# K210_V1.net
KiCad netlist of a schematic drawn in Altium Designer
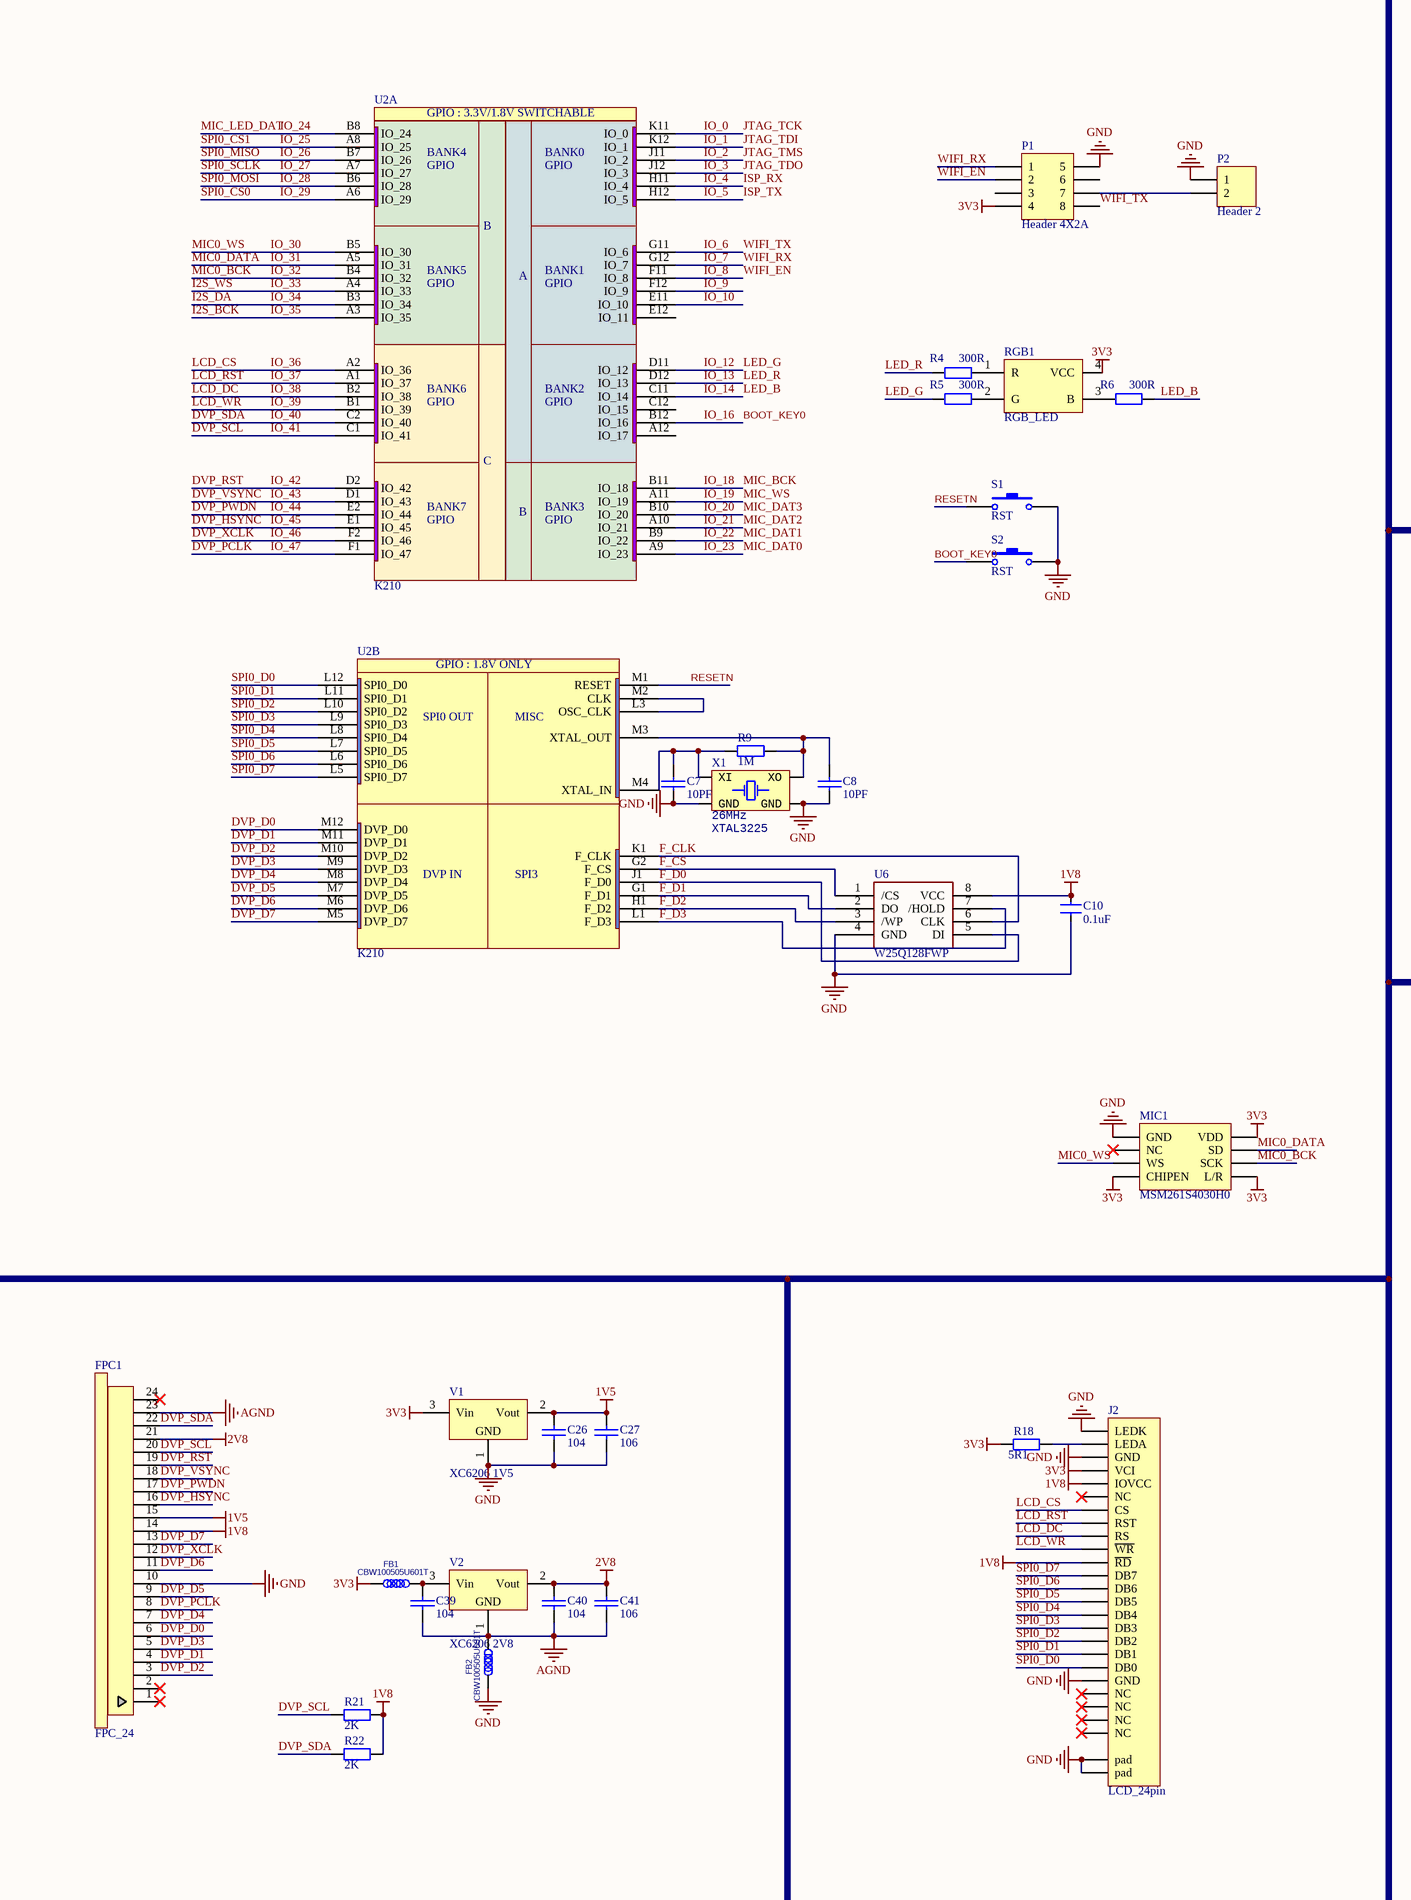
[diagram p0: K210_V1.SchDoc, left]
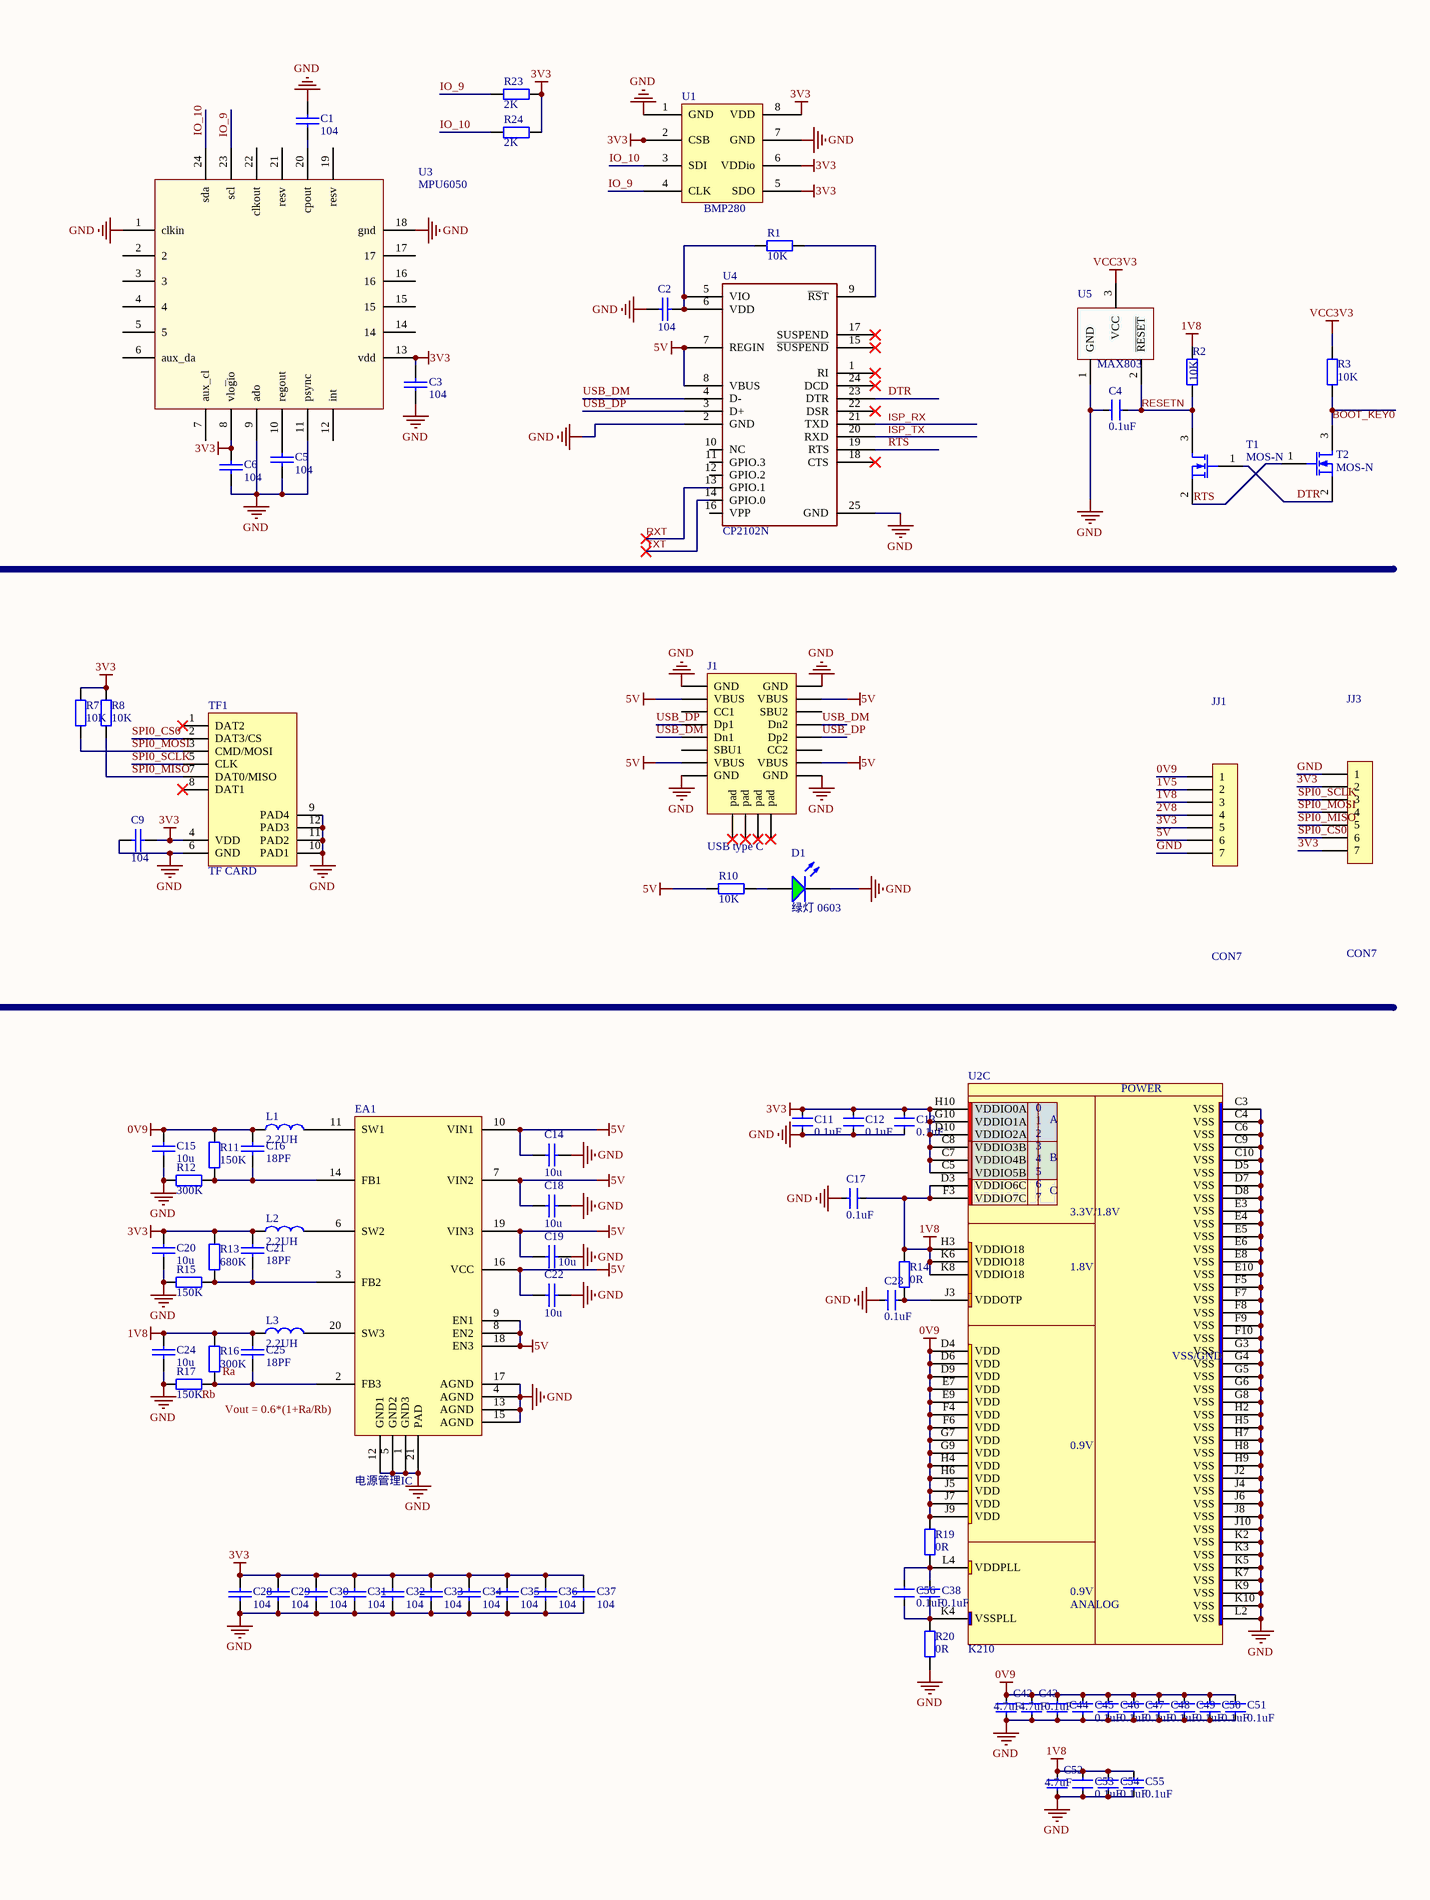
[diagram p1: K210_V1.SchDoc, right]

(export (version "E")
  (design (tool "Eeschema 10.0.6"))
  (components
    (comp (ref "C1") (value "104") (footprint "0603_C") (libsource (lib "XKZ") (part "CAP")))
    (comp (ref "C2") (value "104") (footprint "0603_C") (libsource (lib "XKZ") (part "CAP")))
    (comp (ref "C3") (value "104") (footprint "0603_C") (libsource (lib "XKZ") (part "CAP")))
    (comp (ref "C4")
      (value "0.1uF")
      (footprint "0603_C")
      (description "普通小电容")
      (libsource (lib "LIB_MANGO") (part "CAP"))
    )
    (comp (ref "C5") (value "104") (footprint "0603_C") (libsource (lib "XKZ") (part "CAP")))
    (comp (ref "C6") (value "104") (footprint "0603_C") (libsource (lib "XKZ") (part "CAP")))
    (comp (ref "C7") (value "10PF") (footprint "0603_C") (libsource (lib "XKZ") (part "CAP")))
    (comp (ref "C8") (value "10PF") (footprint "0603_C") (libsource (lib "XKZ") (part "CAP")))
    (comp (ref "C9") (value "104") (footprint "0603_C") (libsource (lib "XKZ") (part "CAP")))
    (comp (ref "C10")
      (value "0.1uF")
      (footprint "0603_C")
      (description "普通小电容")
      (libsource (lib "LIB_MANGO") (part "CAP"))
    )
    (comp (ref "C11")
      (value "0.1uF")
      (footprint "0603_C")
      (description "普通小电容")
      (libsource (lib "LIB_MANGO") (part "CAP"))
    )
    (comp (ref "C12")
      (value "0.1uF")
      (footprint "0603_C")
      (description "普通小电容")
      (libsource (lib "LIB_MANGO") (part "CAP"))
    )
    (comp (ref "C13")
      (value "0.1uF")
      (footprint "0603_C")
      (description "普通小电容")
      (libsource (lib "LIB_MANGO") (part "CAP"))
    )
    (comp (ref "C14") (value "10u") (footprint "0603_C") (libsource (lib "XKZ") (part "CAP")))
    (comp (ref "C15") (value "10u") (footprint "0603_C") (libsource (lib "XKZ") (part "CAP")))
    (comp (ref "C16") (value "18PF") (footprint "0603_C") (libsource (lib "XKZ") (part "CAP")))
    (comp (ref "C17")
      (value "0.1uF")
      (footprint "0603_C")
      (description "普通小电容")
      (libsource (lib "LIB_MANGO") (part "CAP"))
    )
    (comp (ref "C18") (value "10u") (footprint "0603_C") (libsource (lib "XKZ") (part "CAP")))
    (comp (ref "C19") (value "10u") (footprint "0603_C") (libsource (lib "XKZ") (part "CAP")))
    (comp (ref "C20") (value "10u") (footprint "0603_C") (libsource (lib "XKZ") (part "CAP")))
    (comp (ref "C21") (value "18PF") (footprint "0603_C") (libsource (lib "XKZ") (part "CAP")))
    (comp (ref "C22") (value "10u") (footprint "0603_C") (libsource (lib "XKZ") (part "CAP")))
    (comp (ref "C23")
      (value "0.1uF")
      (footprint "0603_C")
      (description "普通小电容")
      (libsource (lib "LIB_MANGO") (part "CAP"))
    )
    (comp (ref "C24") (value "10u") (footprint "0603_C") (libsource (lib "XKZ") (part "CAP")))
    (comp (ref "C25") (value "18PF") (footprint "0603_C") (libsource (lib "XKZ") (part "CAP")))
    (comp (ref "C26") (value "104") (footprint "0603_C") (libsource (lib "XKZ") (part "CAP")))
    (comp (ref "C27") (value "106") (footprint "0603_C") (libsource (lib "XKZ") (part "CAP")))
    (comp (ref "C28") (value "104") (footprint "0603_C") (libsource (lib "XKZ") (part "CAP")))
    (comp (ref "C29") (value "104") (footprint "0603_C") (libsource (lib "XKZ") (part "CAP")))
    (comp (ref "C30") (value "104") (footprint "0603_C") (libsource (lib "XKZ") (part "CAP")))
    (comp (ref "C31") (value "104") (footprint "0603_C") (libsource (lib "XKZ") (part "CAP")))
    (comp (ref "C32") (value "104") (footprint "0603_C") (libsource (lib "XKZ") (part "CAP")))
    (comp (ref "C33") (value "104") (footprint "0603_C") (libsource (lib "XKZ") (part "CAP")))
    (comp (ref "C34") (value "104") (footprint "0603_C") (libsource (lib "XKZ") (part "CAP")))
    (comp (ref "C35") (value "104") (footprint "0603_C") (libsource (lib "XKZ") (part "CAP")))
    (comp (ref "C36") (value "104") (footprint "0603_C") (libsource (lib "XKZ") (part "CAP")))
    (comp (ref "C37") (value "104") (footprint "0603_C") (libsource (lib "XKZ") (part "CAP")))
    (comp (ref "C38")
      (value "0.1uF")
      (footprint "0603_C")
      (description "普通小电容")
      (libsource (lib "LIB_MANGO") (part "CAP"))
    )
    (comp (ref "C39") (value "104") (footprint "0603_C") (libsource (lib "XKZ") (part "CAP")))
    (comp (ref "C40") (value "104") (footprint "0603_C") (libsource (lib "XKZ") (part "CAP")))
    (comp (ref "C41") (value "106") (footprint "0603_C") (libsource (lib "XKZ") (part "CAP")))
    (comp (ref "C42")
      (value "4.7uF")
      (footprint "0603_C")
      (description "普通小电容")
      (libsource (lib "LIB_MANGO") (part "CAP"))
    )
    (comp (ref "C43")
      (value "4.7uF")
      (footprint "0603_C")
      (description "普通小电容")
      (libsource (lib "LIB_MANGO") (part "CAP"))
    )
    (comp (ref "C44")
      (value "0.1uF")
      (footprint "0603_C")
      (description "普通小电容")
      (libsource (lib "LIB_MANGO") (part "CAP"))
    )
    (comp (ref "C45")
      (value "0.1uF")
      (footprint "0603_C")
      (description "普通小电容")
      (libsource (lib "LIB_MANGO") (part "CAP"))
    )
    (comp (ref "C46")
      (value "0.1uF")
      (footprint "0603_C")
      (description "普通小电容")
      (libsource (lib "LIB_MANGO") (part "CAP"))
    )
    (comp (ref "C47")
      (value "0.1uF")
      (footprint "0603_C")
      (description "普通小电容")
      (libsource (lib "LIB_MANGO") (part "CAP"))
    )
    (comp (ref "C48")
      (value "0.1uF")
      (footprint "0603_C")
      (description "普通小电容")
      (libsource (lib "LIB_MANGO") (part "CAP"))
    )
    (comp (ref "C49")
      (value "0.1uF")
      (footprint "0603_C")
      (description "普通小电容")
      (libsource (lib "LIB_MANGO") (part "CAP"))
    )
    (comp (ref "C50")
      (value "0.1uF")
      (footprint "0603_C")
      (description "普通小电容")
      (libsource (lib "LIB_MANGO") (part "CAP"))
    )
    (comp (ref "C51")
      (value "0.1uF")
      (footprint "0603_C")
      (description "普通小电容")
      (libsource (lib "LIB_MANGO") (part "CAP"))
    )
    (comp (ref "C52")
      (value "4.7uF")
      (footprint "0603_C")
      (description "普通小电容")
      (libsource (lib "LIB_MANGO") (part "CAP"))
    )
    (comp (ref "C53")
      (value "0.1uF")
      (footprint "0603_C")
      (description "普通小电容")
      (libsource (lib "LIB_MANGO") (part "CAP"))
    )
    (comp (ref "C54")
      (value "0.1uF")
      (footprint "0603_C")
      (description "普通小电容")
      (libsource (lib "LIB_MANGO") (part "CAP"))
    )
    (comp (ref "C55")
      (value "0.1uF")
      (footprint "0603_C")
      (description "普通小电容")
      (libsource (lib "LIB_MANGO") (part "CAP"))
    )
    (comp (ref "C56")
      (value "0.1uF")
      (footprint "0603_C")
      (description "普通小电容")
      (libsource (lib "LIB_MANGO") (part "CAP"))
    )
    (comp (ref "D1")
      (value "绿灯 0603")
      (footprint "0603_LED")
      (description "发光二极管")
      (libsource (lib "Miscellaneous Devices LC") (part "0603 绿灯"))
    )
    (comp (ref "EA1") (value "电源管理IC") (footprint "QFN20 3x3_M") (libsource (lib "XKZ") (part "EA3036")))
    (comp (ref "FB1") (value "CBW100505U601T") (footprint "0603_R") (libsource (lib "XKZ") (part "FB")))
    (comp (ref "FB2") (value "CBW100505U601T") (footprint "0603_R") (libsource (lib "XKZ") (part "FB")))
    (comp (ref "FPC1") (value "FPC_24") (footprint "FPC_24") (libsource (lib "XKZ") (part "FPC_24")))
    (comp (ref "J1")
      (value "USB type C")
      (footprint "USB Type-C-16Pin_A")
      (libsource (lib "XKZ") (part "USB_C"))
    )
    (comp (ref "J2") (value "LCD_24pin") (footprint "OV7740") (libsource (lib "XKZ") (part "LCD_24pin")))
    (comp (ref "JJ1") (value "CON7") (footprint "HDR2.54-LI-7P") (libsource (lib "XKZ") (part "CON7")))
    (comp (ref "JJ3") (value "CON7") (footprint "HDR2.54-LI-7P") (libsource (lib "XKZ") (part "CON7")))
    (comp (ref "L1")
      (value "2.2UH")
      (footprint "NR3015")
      (description "电感")
      (libsource (lib "XKZ") (part "L1"))
    )
    (comp (ref "L2")
      (value "2.2UH")
      (footprint "NR3015")
      (description "电感")
      (libsource (lib "XKZ") (part "L1"))
    )
    (comp (ref "L3")
      (value "2.2UH")
      (footprint "NR3015")
      (description "电感")
      (libsource (lib "XKZ") (part "L1"))
    )
    (comp (ref "MIC1")
      (value "MSM261S4030H0")
      (footprint "MSM261S4030H0")
      (libsource (lib "XKZ") (part "MSM261S4030H0"))
    )
    (comp (ref "P1")
      (value "Header 4X2A")
      (footprint "HDR2X4_CEN")
      (description "Header, 4-Pin, Dual row")
      (fields (field (name "PUBLISHER") "Altium Limited"))
      (libsource (lib "Miscellaneous Connectors") (part "Header 4X2A"))
    )
    (comp (ref "P2")
      (value "Header 2")
      (footprint "HDR1X2")
      (description "Header, 2-Pin")
      (fields (field (name "PUBLISHER") "Altium Limited"))
      (libsource (lib "Miscellaneous Connectors") (part "Header 2"))
    )
    (comp (ref "R1")
      (value "10K")
      (footprint "0603_R")
      (description "普通电阻")
      (libsource (lib "") (part "RES_2"))
    )
    (comp (ref "R2")
      (value "10K")
      (footprint "0603_R")
      (description "普通电阻")
      (libsource (lib "LIB_MANGO") (part "RES"))
    )
    (comp (ref "R3")
      (value "10K")
      (footprint "0603_R")
      (description "普通电阻")
      (libsource (lib "") (part "RES_1"))
    )
    (comp (ref "R4")
      (value "300R")
      (footprint "0603_R")
      (description "Resistor")
      (fields (field (name "Comment") "1K") (field (name "PUBLISHER") "Altium Limited"))
      (libsource (lib "Miscellaneous Devices") (part "Res2"))
    )
    (comp (ref "R5")
      (value "300R")
      (footprint "0603_R")
      (description "Resistor")
      (fields (field (name "Comment") "1K") (field (name "PUBLISHER") "Altium Limited"))
      (libsource (lib "Miscellaneous Devices") (part "Res2"))
    )
    (comp (ref "R6")
      (value "300R")
      (footprint "0603_R")
      (description "Resistor")
      (fields (field (name "Comment") "1K") (field (name "PUBLISHER") "Altium Limited"))
      (libsource (lib "Miscellaneous Devices") (part "Res2"))
    )
    (comp (ref "R7")
      (value "10K")
      (footprint "0603_R")
      (description "Resistor")
      (fields (field (name "Comment") "Res2") (field (name "PUBLISHER") "Altium Limited"))
      (libsource (lib "XKZ") (part "Res2"))
    )
    (comp (ref "R8")
      (value "10K")
      (footprint "0603_R")
      (description "Resistor")
      (fields (field (name "Comment") "Res2") (field (name "PUBLISHER") "Altium Limited"))
      (libsource (lib "XKZ") (part "Res2"))
    )
    (comp (ref "R9")
      (value "1M")
      (footprint "0603_R")
      (description "Resistor")
      (fields (field (name "Comment") "Res2") (field (name "PUBLISHER") "Altium Limited"))
      (libsource (lib "") (part "Res2_2"))
    )
    (comp (ref "R10")
      (value "10K")
      (footprint "0603_R")
      (description "Resistor")
      (fields (field (name "Comment") "Res2") (field (name "PUBLISHER") "Altium Limited"))
      (libsource (lib "") (part "Res2_1"))
    )
    (comp (ref "R11")
      (value "150K")
      (footprint "0603_R")
      (description "Resistor")
      (fields (field (name "Comment") "Res2") (field (name "PUBLISHER") "Altium Limited"))
      (libsource (lib "") (part "Res2_3"))
    )
    (comp (ref "R12")
      (value "300K")
      (footprint "0603_R")
      (description "Resistor")
      (fields (field (name "Comment") "Res2") (field (name "PUBLISHER") "Altium Limited"))
      (libsource (lib "") (part "Res2_1"))
    )
    (comp (ref "R13")
      (value "680K")
      (footprint "0603_R")
      (description "Resistor")
      (fields (field (name "Comment") "Res2") (field (name "PUBLISHER") "Altium Limited"))
      (libsource (lib "") (part "Res2_3"))
    )
    (comp (ref "R14")
      (value "0R")
      (footprint "0603_R")
      (description "普通电阻")
      (libsource (lib "") (part "RES_1"))
    )
    (comp (ref "R15")
      (value "150K")
      (footprint "0603_R")
      (description "Resistor")
      (fields (field (name "Comment") "Res2") (field (name "PUBLISHER") "Altium Limited"))
      (libsource (lib "") (part "Res2_1"))
    )
    (comp (ref "R16")
      (value "300K")
      (footprint "0603_R")
      (description "Resistor")
      (fields (field (name "Comment") "Res2") (field (name "PUBLISHER") "Altium Limited"))
      (libsource (lib "") (part "Res2_3"))
    )
    (comp (ref "R17")
      (value "150K")
      (footprint "0603_R")
      (description "Resistor")
      (fields (field (name "Comment") "Res2") (field (name "PUBLISHER") "Altium Limited"))
      (libsource (lib "") (part "Res2_1"))
    )
    (comp (ref "R18")
      (value "5R1")
      (footprint "0603_R")
      (description "Resistor")
      (fields (field (name "Comment") "Res2") (field (name "PUBLISHER") "Altium Limited"))
      (libsource (lib "") (part "Res2_2"))
    )
    (comp (ref "R19")
      (value "0R")
      (footprint "0603_R")
      (description "普通电阻")
      (libsource (lib "LIB_MANGO") (part "RES"))
    )
    (comp (ref "R20")
      (value "0R")
      (footprint "0603_R")
      (description "普通电阻")
      (libsource (lib "LIB_MANGO") (part "RES"))
    )
    (comp (ref "R21")
      (value "2K")
      (footprint "0603_R")
      (description "Resistor")
      (fields (field (name "Comment") "Res2") (field (name "PUBLISHER") "Altium Limited"))
      (libsource (lib "") (part "Res2_2"))
    )
    (comp (ref "R22")
      (value "2K")
      (footprint "0603_R")
      (description "Resistor")
      (fields (field (name "Comment") "Res2") (field (name "PUBLISHER") "Altium Limited"))
      (libsource (lib "") (part "Res2_2"))
    )
    (comp (ref "R23")
      (value "2K")
      (footprint "0603_R")
      (description "Resistor")
      (fields (field (name "Comment") "Res2") (field (name "PUBLISHER") "Altium Limited"))
      (libsource (lib "") (part "Res2_2"))
    )
    (comp (ref "R24")
      (value "2K")
      (footprint "0603_R")
      (description "Resistor")
      (fields (field (name "Comment") "Res2") (field (name "PUBLISHER") "Altium Limited"))
      (libsource (lib "") (part "Res2_2"))
    )
    (comp (ref "RGB1")
      (value "RGB_LED")
      (footprint "LED_3528_RGB")
      (description "三色高亮LED")
      (libsource (lib "NT-SchLibrary") (part "RGB_LED"))
    )
    (comp (ref "S1")
      (value "RST")
      (footprint "KEY_1")
      (description "Switch")
      (fields (field (name "PUBLISHER") "Altium Limited"))
      (libsource (lib "自创 (1)") (part "SW-PB"))
    )
    (comp (ref "S2")
      (value "RST")
      (footprint "KEY_1")
      (description "Switch")
      (fields (field (name "PUBLISHER") "Altium Limited"))
      (libsource (lib "自创 (1)") (part "SW-PB"))
    )
    (comp (ref "T1") (value "MOS-N") (footprint "SOT23-3N") (libsource (lib "LIB_MANGO") (part "MOS-N")))
    (comp (ref "T2") (value "MOS-N") (footprint "SOT23-3N") (libsource (lib "LIB_MANGO") (part "MOS-N")))
    (comp (ref "TF1") (value "TF CARD") (footprint "TF卡座") (libsource (lib "XKZ") (part "SD_Card_flip")))
    (comp (ref "U1") (value "BMP280") (footprint "BMP280") (libsource (lib "NT-SchLibrary") (part "BMP280")))
    (comp (ref "U2")
      (value "K210")
      (footprint "BGA144C65P12X12_800X800X95")
      (description "Canaan Kendryte K210 AI SoC")
      (libsource (lib "Vowstar_MCU") (part "K210"))
    )
    (comp (ref "U3")
      (value "MPU6050")
      (footprint "QFN24 4x4_M")
      (libsource (lib "NT-SchLibrary") (part "MPU6050"))
    )
    (comp (ref "U4")
      (value "CP2102N")
      (footprint "QFN24 4x4_N")
      (libsource (lib "LIB_MANGO") (part "CP2104"))
    )
    (comp (ref "U5") (value "MAX803") (footprint "SOT23-3N") (libsource (lib "LIB_MANGO") (part "MAX809")))
    (comp (ref "U6")
      (value "W25Q128FWP")
      (footprint "WSON8")
      (libsource (lib "LIB_MANGO") (part "SPIFLASH_SOP8W"))
    )
    (comp (ref "V1")
      (value "XC6206 1V5")
      (footprint "SOT23-3N")
      (description "低压差线性稳压芯片")
      (fields (field (name "版权归属") "源创客"))
      (libsource (lib "XKZ") (part "XC6206P332MR"))
    )
    (comp (ref "V2")
      (value "XC6206 2V8")
      (footprint "SOT23-3N")
      (description "低压差线性稳压芯片")
      (fields (field (name "版权归属") "源创客"))
      (libsource (lib "XKZ") (part "XC6206P332MR"))
    )
    (comp (ref "X1")
      (value "26MHz")
      (footprint "XT_3225_4")
      (description "Crystal Oscillator")
      (fields (field (name "TYPE") "XTAL3225"))
      (libsource (lib "XKZ") (part "XTAL_3225_4P"))
    )
  )
  (nets
    (net (code "1") (name "/BOOT_KEY0") (class "Default")
      (node (ref "R3") (pin "2") (pinfunction "2_2") (pintype "passive"))
      (node (ref "S2") (pin "1") (pinfunction "1_1") (pintype "passive"))
      (node (ref "T2") (pin "3") (pinfunction "3_3") (pintype "passive"))
      (node (ref "U2") (pin "B12") (pinfunction "IO_16_B12") (pintype "passive"))
    )
    (net (code "2") (name "/DTR") (class "Default")
      (node (ref "T1") (pin "1") (pinfunction "1_1") (pintype "passive"))
      (node (ref "T2") (pin "2") (pinfunction "2_2") (pintype "passive"))
      (node (ref "U4") (pin "23") (pinfunction "DTR_23") (pintype "passive"))
    )
    (net (code "3") (name "/DVP_D0") (class "Default")
      (node (ref "FPC1") (pin "6") (pinfunction "6_6") (pintype "passive"))
      (node (ref "U2") (pin "M12") (pinfunction "DVP_D0_M12") (pintype "passive"))
    )
    (net (code "4") (name "/DVP_D1") (class "Default")
      (node (ref "FPC1") (pin "4") (pinfunction "4_4") (pintype "passive"))
      (node (ref "U2") (pin "M11") (pinfunction "DVP_D1_M11") (pintype "passive"))
    )
    (net (code "5") (name "/DVP_D2") (class "Default")
      (node (ref "FPC1") (pin "3") (pinfunction "3_3") (pintype "passive"))
      (node (ref "U2") (pin "M10") (pinfunction "DVP_D2_M10") (pintype "passive"))
    )
    (net (code "6") (name "/DVP_D3") (class "Default")
      (node (ref "FPC1") (pin "5") (pinfunction "5_5") (pintype "passive"))
      (node (ref "U2") (pin "M9") (pinfunction "DVP_D3_M9") (pintype "passive"))
    )
    (net (code "7") (name "/DVP_D4") (class "Default")
      (node (ref "FPC1") (pin "7") (pinfunction "7_7") (pintype "passive"))
      (node (ref "U2") (pin "M8") (pinfunction "DVP_D4_M8") (pintype "passive"))
    )
    (net (code "8") (name "/DVP_D5") (class "Default")
      (node (ref "FPC1") (pin "9") (pinfunction "9_9") (pintype "passive"))
      (node (ref "U2") (pin "M7") (pinfunction "DVP_D5_M7") (pintype "passive"))
    )
    (net (code "9") (name "/DVP_D6") (class "Default")
      (node (ref "FPC1") (pin "11") (pinfunction "11_11") (pintype "passive"))
      (node (ref "U2") (pin "M6") (pinfunction "DVP_D6_M6") (pintype "passive"))
    )
    (net (code "10") (name "/DVP_D7") (class "Default")
      (node (ref "FPC1") (pin "13") (pinfunction "13_13") (pintype "passive"))
      (node (ref "U2") (pin "M5") (pinfunction "DVP_D7_M5") (pintype "passive"))
    )
    (net (code "11") (name "/DVP_HSYNC") (class "Default")
      (node (ref "FPC1") (pin "16") (pinfunction "16_16") (pintype "passive"))
      (node (ref "U2") (pin "E1") (pinfunction "IO_45_E1") (pintype "passive"))
    )
    (net (code "12") (name "/DVP_PCLK") (class "Default")
      (node (ref "FPC1") (pin "8") (pinfunction "8_8") (pintype "passive"))
      (node (ref "U2") (pin "F1") (pinfunction "IO_47_F1") (pintype "passive"))
    )
    (net (code "13") (name "/DVP_PWDN") (class "Default")
      (node (ref "FPC1") (pin "17") (pinfunction "17_17") (pintype "passive"))
      (node (ref "U2") (pin "E2") (pinfunction "IO_44_E2") (pintype "passive"))
    )
    (net (code "14") (name "/DVP_RST") (class "Default")
      (node (ref "FPC1") (pin "19") (pinfunction "19_19") (pintype "passive"))
      (node (ref "U2") (pin "D2") (pinfunction "IO_42_D2") (pintype "passive"))
    )
    (net (code "15") (name "/DVP_SCL") (class "Default")
      (node (ref "FPC1") (pin "20") (pinfunction "20_20") (pintype "passive"))
      (node (ref "R21") (pin "2") (pinfunction "2_2") (pintype "passive"))
      (node (ref "U2") (pin "C1") (pinfunction "IO_41_C1") (pintype "passive"))
    )
    (net (code "16") (name "/DVP_SDA") (class "Default")
      (node (ref "FPC1") (pin "22") (pinfunction "22_22") (pintype "passive"))
      (node (ref "R22") (pin "2") (pinfunction "2_2") (pintype "passive"))
      (node (ref "U2") (pin "C2") (pinfunction "IO_40_C2") (pintype "passive"))
    )
    (net (code "17") (name "/DVP_VSYNC") (class "Default")
      (node (ref "FPC1") (pin "18") (pinfunction "18_18") (pintype "passive"))
      (node (ref "U2") (pin "D1") (pinfunction "IO_43_D1") (pintype "passive"))
    )
    (net (code "18") (name "/DVP_XCLK") (class "Default")
      (node (ref "FPC1") (pin "12") (pinfunction "12_12") (pintype "passive"))
      (node (ref "U2") (pin "F2") (pinfunction "IO_46_F2") (pintype "passive"))
    )
    (net (code "19") (name "/F_CLK") (class "Default")
      (node (ref "U2") (pin "K1") (pinfunction "F_CLK_K1") (pintype "passive"))
      (node (ref "U6") (pin "6") (pinfunction "CLK_6") (pintype "passive"))
    )
    (net (code "20") (name "/F_CS") (class "Default")
      (node (ref "U2") (pin "G2") (pinfunction "F_CS_G2") (pintype "passive"))
      (node (ref "U6") (pin "1") (pinfunction "/CS_1") (pintype "passive"))
    )
    (net (code "21") (name "/F_D0") (class "Default")
      (node (ref "U2") (pin "J1") (pinfunction "F_D0_J1") (pintype "passive"))
      (node (ref "U6") (pin "5") (pinfunction "DI_5") (pintype "passive"))
    )
    (net (code "22") (name "/F_D1") (class "Default")
      (node (ref "U2") (pin "G1") (pinfunction "F_D1_G1") (pintype "passive"))
      (node (ref "U6") (pin "2") (pinfunction "DO_2") (pintype "passive"))
    )
    (net (code "23") (name "/F_D2") (class "Default")
      (node (ref "U2") (pin "H1") (pinfunction "F_D2_H1") (pintype "passive"))
      (node (ref "U6") (pin "3") (pinfunction "/WP_3") (pintype "passive"))
    )
    (net (code "24") (name "/F_D3") (class "Default")
      (node (ref "U2") (pin "L1") (pinfunction "F_D3_L1") (pintype "passive"))
      (node (ref "U6") (pin "7") (pinfunction "/HOLD_7") (pintype "passive"))
    )
    (net (code "25") (name "/I2S_BCK") (class "Default")
      (node (ref "U2") (pin "A3") (pinfunction "IO_35_A3") (pintype "passive"))
    )
    (net (code "26") (name "/I2S_DA") (class "Default")
      (node (ref "U2") (pin "B3") (pinfunction "IO_34_B3") (pintype "passive"))
    )
    (net (code "27") (name "/I2S_WS") (class "Default")
      (node (ref "U2") (pin "A4") (pinfunction "IO_33_A4") (pintype "passive"))
    )
    (net (code "28") (name "/IO_0") (class "Default")
      (node (ref "U2") (pin "K11") (pinfunction "IO_0_K11") (pintype "passive"))
    )
    (net (code "29") (name "/IO_1") (class "Default")
      (node (ref "U2") (pin "K12") (pinfunction "IO_1_K12") (pintype "passive"))
    )
    (net (code "30") (name "/IO_2") (class "Default")
      (node (ref "U2") (pin "J11") (pinfunction "IO_2_J11") (pintype "passive"))
    )
    (net (code "31") (name "/IO_3") (class "Default")
      (node (ref "U2") (pin "J12") (pinfunction "IO_3_J12") (pintype "passive"))
    )
    (net (code "32") (name "/IO_4") (class "Default")
      (node (ref "U2") (pin "H11") (pinfunction "IO_4_H11") (pintype "passive"))
      (node (ref "U4") (pin "21") (pinfunction "TXD_21") (pintype "passive"))
    )
    (net (code "33") (name "/IO_5") (class "Default")
      (node (ref "U2") (pin "H12") (pinfunction "IO_5_H12") (pintype "passive"))
      (node (ref "U4") (pin "20") (pinfunction "RXD_20") (pintype "passive"))
    )
    (net (code "34") (name "/IO_6") (class "Default")
      (node (ref "P1") (pin "8") (pinfunction "8_8") (pintype "passive"))
      (node (ref "U2") (pin "G11") (pinfunction "IO_6_G11") (pintype "passive"))
    )
    (net (code "35") (name "/IO_7") (class "Default")
      (node (ref "P1") (pin "1") (pinfunction "1_1") (pintype "passive"))
      (node (ref "U2") (pin "G12") (pinfunction "IO_7_G12") (pintype "passive"))
    )
    (net (code "36") (name "/IO_8") (class "Default")
      (node (ref "P1") (pin "2") (pinfunction "2_2") (pintype "passive"))
      (node (ref "U2") (pin "F11") (pinfunction "IO_8_F11") (pintype "passive"))
    )
    (net (code "37") (name "/IO_9") (class "Default")
      (node (ref "R23") (pin "2") (pinfunction "2_2") (pintype "passive"))
      (node (ref "U1") (pin "4") (pinfunction "CLK_4") (pintype "power_in"))
      (node (ref "U2") (pin "F12") (pinfunction "IO_9_F12") (pintype "passive"))
      (node (ref "U3") (pin "23") (pinfunction "scl_23") (pintype "passive"))
    )
    (net (code "38") (name "/IO_10") (class "Default")
      (node (ref "R24") (pin "2") (pinfunction "2_2") (pintype "passive"))
      (node (ref "U1") (pin "3") (pinfunction "SDI_3") (pintype "passive"))
      (node (ref "U2") (pin "E11") (pinfunction "IO_10_E11") (pintype "passive"))
      (node (ref "U3") (pin "24") (pinfunction "sda_24") (pintype "passive"))
    )
    (net (code "39") (name "/IO_12") (class "Default")
      (node (ref "R5") (pin "1") (pinfunction "1_1") (pintype "passive"))
      (node (ref "U2") (pin "D11") (pinfunction "IO_12_D11") (pintype "passive"))
    )
    (net (code "40") (name "/IO_13") (class "Default")
      (node (ref "R4") (pin "1") (pinfunction "1_1") (pintype "passive"))
      (node (ref "U2") (pin "D12") (pinfunction "IO_13_D12") (pintype "passive"))
    )
    (net (code "41") (name "/IO_14") (class "Default")
      (node (ref "R6") (pin "2") (pinfunction "2_2") (pintype "passive"))
      (node (ref "U2") (pin "C11") (pinfunction "IO_14_C11") (pintype "passive"))
    )
    (net (code "42") (name "/IO_18") (class "Default")
      (node (ref "U2") (pin "B11") (pinfunction "IO_18_B11") (pintype "passive"))
    )
    (net (code "43") (name "/IO_19") (class "Default")
      (node (ref "U2") (pin "A11") (pinfunction "IO_19_A11") (pintype "passive"))
    )
    (net (code "44") (name "/IO_20") (class "Default")
      (node (ref "U2") (pin "B10") (pinfunction "IO_20_B10") (pintype "passive"))
    )
    (net (code "45") (name "/IO_21") (class "Default")
      (node (ref "U2") (pin "A10") (pinfunction "IO_21_A10") (pintype "passive"))
    )
    (net (code "46") (name "/IO_22") (class "Default")
      (node (ref "U2") (pin "B9") (pinfunction "IO_22_B9") (pintype "passive"))
    )
    (net (code "47") (name "/IO_23") (class "Default")
      (node (ref "U2") (pin "A9") (pinfunction "IO_23_A9") (pintype "passive"))
    )
    (net (code "48") (name "/IO_24") (class "Default")
      (node (ref "U2") (pin "B8") (pinfunction "IO_24_B8") (pintype "passive"))
    )
    (net (code "49") (name "/IO_25") (class "Default")
      (node (ref "U2") (pin "A8") (pinfunction "IO_25_A8") (pintype "passive"))
    )
    (net (code "50") (name "/IO_26") (class "Default")
      (node (ref "JJ3") (pin "5") (pinfunction "5_5") (pintype "passive"))
      (node (ref "R8") (pin "2") (pinfunction "2_2") (pintype "passive"))
      (node (ref "TF1") (pin "7") (pinfunction "DAT0/MISO_7") (pintype "passive"))
      (node (ref "U2") (pin "B7") (pinfunction "IO_26_B7") (pintype "passive"))
    )
    (net (code "51") (name "/IO_27") (class "Default")
      (node (ref "JJ3") (pin "3") (pinfunction "3_3") (pintype "passive"))
      (node (ref "TF1") (pin "5") (pinfunction "CLK_5") (pintype "passive"))
      (node (ref "U2") (pin "A7") (pinfunction "IO_27_A7") (pintype "passive"))
    )
    (net (code "52") (name "/IO_28") (class "Default")
      (node (ref "JJ3") (pin "4") (pinfunction "4_4") (pintype "passive"))
      (node (ref "R7") (pin "2") (pinfunction "2_2") (pintype "passive"))
      (node (ref "TF1") (pin "3") (pinfunction "CMD/MOSI_3") (pintype "passive"))
      (node (ref "U2") (pin "B6") (pinfunction "IO_28_B6") (pintype "passive"))
    )
    (net (code "53") (name "/IO_29") (class "Default")
      (node (ref "JJ3") (pin "6") (pinfunction "6_6") (pintype "passive"))
      (node (ref "TF1") (pin "2") (pinfunction "DAT3/CS_2") (pintype "passive"))
      (node (ref "U2") (pin "A6") (pinfunction "IO_29_A6") (pintype "passive"))
    )
    (net (code "54") (name "/IO_30") (class "Default")
      (node (ref "MIC1") (pin "3") (pinfunction "WS_3") (pintype "passive"))
      (node (ref "U2") (pin "B5") (pinfunction "IO_30_B5") (pintype "passive"))
    )
    (net (code "55") (name "/IO_31") (class "Default")
      (node (ref "MIC1") (pin "7") (pinfunction "SD_7") (pintype "passive"))
      (node (ref "U2") (pin "A5") (pinfunction "IO_31_A5") (pintype "passive"))
    )
    (net (code "56") (name "/IO_32") (class "Default")
      (node (ref "MIC1") (pin "6") (pinfunction "SCK_6") (pintype "passive"))
      (node (ref "U2") (pin "B4") (pinfunction "IO_32_B4") (pintype "passive"))
    )
    (net (code "57") (name "/IO_36") (class "Default")
      (node (ref "J2") (pin "7") (pinfunction "CS_7") (pintype "passive"))
      (node (ref "U2") (pin "A2") (pinfunction "IO_36_A2") (pintype "passive"))
    )
    (net (code "58") (name "/IO_37") (class "Default")
      (node (ref "J2") (pin "8") (pinfunction "RST_8") (pintype "passive"))
      (node (ref "U2") (pin "A1") (pinfunction "IO_37_A1") (pintype "passive"))
    )
    (net (code "59") (name "/IO_38") (class "Default")
      (node (ref "J2") (pin "9") (pinfunction "RS_9") (pintype "passive"))
      (node (ref "U2") (pin "B2") (pinfunction "IO_38_B2") (pintype "passive"))
    )
    (net (code "60") (name "/IO_39") (class "Default")
      (node (ref "J2") (pin "10") (pinfunction "~{WR}_10") (pintype "passive"))
      (node (ref "U2") (pin "B1") (pinfunction "IO_39_B1") (pintype "passive"))
    )
    (net (code "61") (name "/RESETN") (class "Default")
      (node (ref "C4") (pin "2") (pinfunction "2_2") (pintype "passive"))
      (node (ref "R2") (pin "1") (pinfunction "1_1") (pintype "passive"))
      (node (ref "S1") (pin "1") (pinfunction "1_1") (pintype "passive"))
      (node (ref "T1") (pin "3") (pinfunction "3_3") (pintype "passive"))
      (node (ref "U2") (pin "M1") (pinfunction "RESET_M1") (pintype "passive"))
      (node (ref "U5") (pin "2") (pinfunction "~{RESET}_2") (pintype "passive"))
    )
    (net (code "62") (name "/RTS") (class "Default")
      (node (ref "T1") (pin "2") (pinfunction "2_2") (pintype "passive"))
      (node (ref "T2") (pin "1") (pinfunction "1_1") (pintype "passive"))
      (node (ref "U4") (pin "19") (pinfunction "RTS_19") (pintype "passive"))
    )
    (net (code "63") (name "/RXT") (class "Default")
      (node (ref "U4") (pin "13") (pinfunction "GPIO.1_13") (pintype "passive+no_connect"))
    )
    (net (code "66") (name "/SPI0_D0") (class "Default")
      (node (ref "J2") (pin "19") (pinfunction "DB0_19") (pintype "passive"))
      (node (ref "U2") (pin "L12") (pinfunction "SPI0_D0_L12") (pintype "passive"))
    )
    (net (code "67") (name "/SPI0_D1") (class "Default")
      (node (ref "J2") (pin "18") (pinfunction "DB1_18") (pintype "passive"))
      (node (ref "U2") (pin "L11") (pinfunction "SPI0_D1_L11") (pintype "passive"))
    )
    (net (code "68") (name "/SPI0_D2") (class "Default")
      (node (ref "J2") (pin "17") (pinfunction "DB2_17") (pintype "passive"))
      (node (ref "U2") (pin "L10") (pinfunction "SPI0_D2_L10") (pintype "passive"))
    )
    (net (code "69") (name "/SPI0_D3") (class "Default")
      (node (ref "J2") (pin "16") (pinfunction "DB3_16") (pintype "passive"))
      (node (ref "U2") (pin "L9") (pinfunction "SPI0_D3_L9") (pintype "passive"))
    )
    (net (code "70") (name "/SPI0_D4") (class "Default")
      (node (ref "J2") (pin "15") (pinfunction "DB4_15") (pintype "passive"))
      (node (ref "U2") (pin "L8") (pinfunction "SPI0_D4_L8") (pintype "passive"))
    )
    (net (code "71") (name "/SPI0_D5") (class "Default")
      (node (ref "J2") (pin "14") (pinfunction "DB5_14") (pintype "passive"))
      (node (ref "U2") (pin "L7") (pinfunction "SPI0_D5_L7") (pintype "passive"))
    )
    (net (code "72") (name "/SPI0_D6") (class "Default")
      (node (ref "J2") (pin "13") (pinfunction "DB6_13") (pintype "passive"))
      (node (ref "U2") (pin "L6") (pinfunction "SPI0_D6_L6") (pintype "passive"))
    )
    (net (code "73") (name "/SPI0_D7") (class "Default")
      (node (ref "J2") (pin "12") (pinfunction "DB7_12") (pintype "passive"))
      (node (ref "U2") (pin "L5") (pinfunction "SPI0_D7_L5") (pintype "passive"))
    )
    (net (code "74") (name "/TXT") (class "Default")
      (node (ref "U4") (pin "14") (pinfunction "GPIO.0_14") (pintype "passive+no_connect"))
    )
    (net (code "75") (name "/USB_DM") (class "Default")
      (node (ref "J1") (pin "A7") (pinfunction "Dn1_A7") (pintype "passive"))
      (node (ref "J1") (pin "B7") (pinfunction "Dn2_B7") (pintype "passive"))
      (node (ref "U4") (pin "4") (pinfunction "D-_4") (pintype "passive"))
    )
    (net (code "76") (name "/USB_DP") (class "Default")
      (node (ref "J1") (pin "A6") (pinfunction "Dp1_A6") (pintype "passive"))
      (node (ref "J1") (pin "B6") (pinfunction "Dp2_B6") (pintype "passive"))
      (node (ref "U4") (pin "3") (pinfunction "D+_3") (pintype "passive"))
    )
    (net (code "78") (name "0V9") (class "Default")
      (node (ref "C15") (pin "1") (pinfunction "1_1") (pintype "passive"))
      (node (ref "C16") (pin "1") (pinfunction "1_1") (pintype "passive"))
      (node (ref "C42") (pin "2") (pinfunction "2_2") (pintype "passive"))
      (node (ref "C43") (pin "2") (pinfunction "2_2") (pintype "passive"))
      (node (ref "C44") (pin "2") (pinfunction "2_2") (pintype "passive"))
      (node (ref "C45") (pin "2") (pinfunction "2_2") (pintype "passive"))
      (node (ref "C46") (pin "2") (pinfunction "2_2") (pintype "passive"))
      (node (ref "C47") (pin "2") (pinfunction "2_2") (pintype "passive"))
      (node (ref "C48") (pin "2") (pinfunction "2_2") (pintype "passive"))
      (node (ref "C49") (pin "2") (pinfunction "2_2") (pintype "passive"))
      (node (ref "C50") (pin "2") (pinfunction "2_2") (pintype "passive"))
      (node (ref "C51") (pin "2") (pinfunction "2_2") (pintype "passive"))
      (node (ref "JJ1") (pin "1") (pinfunction "1_1") (pintype "passive"))
      (node (ref "L1") (pin "2") (pinfunction "2_2") (pintype "passive"))
      (node (ref "R11") (pin "2") (pinfunction "2_2") (pintype "passive"))
      (node (ref "R19") (pin "2") (pinfunction "2_2") (pintype "passive"))
      (node (ref "U2") (pin "D4") (pinfunction "VDD_D4") (pintype "power_in"))
      (node (ref "U2") (pin "D6") (pinfunction "VDD_D6") (pintype "power_in"))
      (node (ref "U2") (pin "D9") (pinfunction "VDD_D9") (pintype "power_in"))
      (node (ref "U2") (pin "E7") (pinfunction "VDD_E7") (pintype "power_in"))
      (node (ref "U2") (pin "E9") (pinfunction "VDD_E9") (pintype "power_in"))
      (node (ref "U2") (pin "F4") (pinfunction "VDD_F4") (pintype "power_in"))
      (node (ref "U2") (pin "F6") (pinfunction "VDD_F6") (pintype "power_in"))
      (node (ref "U2") (pin "G7") (pinfunction "VDD_G7") (pintype "power_in"))
      (node (ref "U2") (pin "G9") (pinfunction "VDD_G9") (pintype "power_in"))
      (node (ref "U2") (pin "H4") (pinfunction "VDD_H4") (pintype "power_in"))
      (node (ref "U2") (pin "H6") (pinfunction "VDD_H6") (pintype "power_in"))
      (node (ref "U2") (pin "J5") (pinfunction "VDD_J5") (pintype "power_in"))
      (node (ref "U2") (pin "J7") (pinfunction "VDD_J7") (pintype "power_in"))
      (node (ref "U2") (pin "J9") (pinfunction "VDD_J9") (pintype "power_in"))
    )
    (net (code "79") (name "1V5") (class "Default")
      (node (ref "C26") (pin "1") (pinfunction "1_1") (pintype "passive"))
      (node (ref "C27") (pin "1") (pinfunction "1_1") (pintype "passive"))
      (node (ref "FPC1") (pin "15") (pinfunction "15_15") (pintype "passive"))
      (node (ref "JJ1") (pin "2") (pinfunction "2_2") (pintype "passive"))
      (node (ref "V1") (pin "2") (pinfunction "Vout_2") (pintype "passive"))
    )
    (net (code "80") (name "1V8") (class "Default")
      (node (ref "C10") (pin "2") (pinfunction "2_2") (pintype "passive"))
      (node (ref "C17") (pin "1") (pinfunction "1_1") (pintype "passive"))
      (node (ref "C24") (pin "1") (pinfunction "1_1") (pintype "passive"))
      (node (ref "C25") (pin "1") (pinfunction "1_1") (pintype "passive"))
      (node (ref "C52") (pin "2") (pinfunction "2_2") (pintype "passive"))
      (node (ref "C53") (pin "2") (pinfunction "2_2") (pintype "passive"))
      (node (ref "C54") (pin "2") (pinfunction "2_2") (pintype "passive"))
      (node (ref "C55") (pin "2") (pinfunction "2_2") (pintype "passive"))
      (node (ref "FPC1") (pin "14") (pinfunction "14_14") (pintype "passive"))
      (node (ref "J2") (pin "11") (pinfunction "~{RD}_11") (pintype "passive"))
      (node (ref "J2") (pin "5") (pinfunction "IOVCC_5") (pintype "passive"))
      (node (ref "JJ1") (pin "3") (pinfunction "3_3") (pintype "passive"))
      (node (ref "L3") (pin "2") (pinfunction "2_2") (pintype "passive"))
      (node (ref "R14") (pin "1") (pinfunction "1_1") (pintype "passive"))
      (node (ref "R16") (pin "2") (pinfunction "2_2") (pintype "passive"))
      (node (ref "R2") (pin "2") (pinfunction "2_2") (pintype "passive"))
      (node (ref "R21") (pin "1") (pinfunction "1_1") (pintype "passive"))
      (node (ref "R22") (pin "1") (pinfunction "1_1") (pintype "passive"))
      (node (ref "U2") (pin "D3") (pinfunction "VDDIO6C_D3") (pintype "power_in"))
      (node (ref "U2") (pin "F3") (pinfunction "VDDIO7C_F3") (pintype "power_in"))
      (node (ref "U2") (pin "H3") (pinfunction "VDDIO18_H3") (pintype "power_in"))
      (node (ref "U2") (pin "K6") (pinfunction "VDDIO18_K6") (pintype "power_in"))
      (node (ref "U2") (pin "K8") (pinfunction "VDDIO18_K8") (pintype "power_in"))
      (node (ref "U6") (pin "8") (pinfunction "VCC_8") (pintype "passive"))
    )
    (net (code "81") (name "2V8") (class "Default")
      (node (ref "C40") (pin "1") (pinfunction "1_1") (pintype "passive"))
      (node (ref "C41") (pin "1") (pinfunction "1_1") (pintype "passive"))
      (node (ref "FPC1") (pin "21") (pinfunction "21_21") (pintype "passive"))
      (node (ref "JJ1") (pin "4") (pinfunction "4_4") (pintype "passive"))
      (node (ref "V2") (pin "2") (pinfunction "Vout_2") (pintype "passive"))
    )
    (net (code "82") (name "3V3") (class "Default")
      (node (ref "C11") (pin "1") (pinfunction "1_1") (pintype "passive"))
      (node (ref "C12") (pin "1") (pinfunction "1_1") (pintype "passive"))
      (node (ref "C13") (pin "1") (pinfunction "1_1") (pintype "passive"))
      (node (ref "C20") (pin "1") (pinfunction "1_1") (pintype "passive"))
      (node (ref "C21") (pin "1") (pinfunction "1_1") (pintype "passive"))
      (node (ref "C28") (pin "1") (pinfunction "1_1") (pintype "passive"))
      (node (ref "C29") (pin "1") (pinfunction "1_1") (pintype "passive"))
      (node (ref "C3") (pin "2") (pinfunction "2_2") (pintype "passive"))
      (node (ref "C30") (pin "1") (pinfunction "1_1") (pintype "passive"))
      (node (ref "C31") (pin "1") (pinfunction "1_1") (pintype "passive"))
      (node (ref "C32") (pin "1") (pinfunction "1_1") (pintype "passive"))
      (node (ref "C33") (pin "1") (pinfunction "1_1") (pintype "passive"))
      (node (ref "C34") (pin "1") (pinfunction "1_1") (pintype "passive"))
      (node (ref "C35") (pin "1") (pinfunction "1_1") (pintype "passive"))
      (node (ref "C36") (pin "1") (pinfunction "1_1") (pintype "passive"))
      (node (ref "C37") (pin "1") (pinfunction "1_1") (pintype "passive"))
      (node (ref "C6") (pin "2") (pinfunction "2_2") (pintype "passive"))
      (node (ref "C9") (pin "2") (pinfunction "2_2") (pintype "passive"))
      (node (ref "FB1") (pin "2") (pinfunction "2_2") (pintype "passive"))
      (node (ref "J2") (pin "4") (pinfunction "VCI_4") (pintype "passive"))
      (node (ref "JJ1") (pin "5") (pinfunction "5_5") (pintype "passive"))
      (node (ref "JJ3") (pin "2") (pinfunction "2_2") (pintype "passive"))
      (node (ref "JJ3") (pin "7") (pinfunction "7_7") (pintype "passive"))
      (node (ref "L2") (pin "2") (pinfunction "2_2") (pintype "passive"))
      (node (ref "MIC1") (pin "4") (pinfunction "CHIPEN_4") (pintype "passive"))
      (node (ref "MIC1") (pin "5") (pinfunction "L/R_5") (pintype "passive"))
      (node (ref "MIC1") (pin "8") (pinfunction "VDD_8") (pintype "passive"))
      (node (ref "P1") (pin "4") (pinfunction "4_4") (pintype "passive"))
      (node (ref "R13") (pin "2") (pinfunction "2_2") (pintype "passive"))
      (node (ref "R18") (pin "2") (pinfunction "2_2") (pintype "passive"))
      (node (ref "R23") (pin "1") (pinfunction "1_1") (pintype "passive"))
      (node (ref "R24") (pin "1") (pinfunction "1_1") (pintype "passive"))
      (node (ref "R7") (pin "1") (pinfunction "1_1") (pintype "passive"))
      (node (ref "R8") (pin "1") (pinfunction "1_1") (pintype "passive"))
      (node (ref "RGB1") (pin "4") (pinfunction "VCC_4") (pintype "passive"))
      (node (ref "TF1") (pin "4") (pinfunction "VDD_4") (pintype "passive"))
      (node (ref "U1") (pin "2") (pinfunction "CSB_2") (pintype "passive"))
      (node (ref "U1") (pin "5") (pinfunction "SDO_5") (pintype "passive"))
      (node (ref "U1") (pin "6") (pinfunction "VDDio_6") (pintype "passive"))
      (node (ref "U1") (pin "8") (pinfunction "VDD_8") (pintype "power_in"))
      (node (ref "U2") (pin "C5") (pinfunction "VDDIO5B_C5") (pintype "power_in"))
      (node (ref "U2") (pin "C7") (pinfunction "VDDIO4B_C7") (pintype "power_in"))
      (node (ref "U2") (pin "C8") (pinfunction "VDDIO3B_C8") (pintype "power_in"))
      (node (ref "U2") (pin "D10") (pinfunction "VDDIO2A_D10") (pintype "power_in"))
      (node (ref "U2") (pin "G10") (pinfunction "VDDIO1A_G10") (pintype "power_in"))
      (node (ref "U2") (pin "H10") (pinfunction "VDDIO0A_H10") (pintype "power_in"))
      (node (ref "U3") (pin "13") (pinfunction "vdd_13") (pintype "passive"))
      (node (ref "U3") (pin "8") (pinfunction "vlo~{g}io_8") (pintype "passive"))
      (node (ref "V1") (pin "3") (pinfunction "Vin_3") (pintype "passive"))
    )
    (net (code "83") (name "5V") (class "Default")
      (node (ref "C14") (pin "1") (pinfunction "1_1") (pintype "passive"))
      (node (ref "C18") (pin "1") (pinfunction "1_1") (pintype "passive"))
      (node (ref "C19") (pin "1") (pinfunction "1_1") (pintype "passive"))
      (node (ref "C22") (pin "1") (pinfunction "1_1") (pintype "passive"))
      (node (ref "EA1") (pin "10") (pinfunction "VIN1_10") (pintype "passive"))
      (node (ref "EA1") (pin "16") (pinfunction "VCC_16") (pintype "passive"))
      (node (ref "EA1") (pin "18") (pinfunction "EN3_18") (pintype "passive"))
      (node (ref "EA1") (pin "19") (pinfunction "VIN3_19") (pintype "passive"))
      (node (ref "EA1") (pin "7") (pinfunction "VIN2_7") (pintype "passive"))
      (node (ref "EA1") (pin "8") (pinfunction "EN2_8") (pintype "passive"))
      (node (ref "EA1") (pin "9") (pinfunction "EN1_9") (pintype "passive"))
      (node (ref "J1") (pin "A4") (pinfunction "VBUS_A4") (pintype "passive"))
      (node (ref "J1") (pin "A9") (pinfunction "VBUS_A9") (pintype "passive"))
      (node (ref "J1") (pin "B4") (pinfunction "VBUS_B4") (pintype "passive"))
      (node (ref "J1") (pin "B9") (pinfunction "VBUS_B9") (pintype "passive"))
      (node (ref "JJ1") (pin "6") (pinfunction "6_6") (pintype "passive"))
      (node (ref "R10") (pin "1") (pinfunction "1_1") (pintype "passive"))
      (node (ref "U4") (pin "7") (pinfunction "REGIN_7") (pintype "passive"))
      (node (ref "U4") (pin "8") (pinfunction "VBUS_8") (pintype "power_in"))
    )
    (net (code "84") (name "AGND") (class "Default")
      (node (ref "C39") (pin "2") (pinfunction "2_2") (pintype "passive"))
      (node (ref "C40") (pin "2") (pinfunction "2_2") (pintype "passive"))
      (node (ref "C41") (pin "2") (pinfunction "2_2") (pintype "passive"))
      (node (ref "FB2") (pin "1") (pinfunction "1_1") (pintype "passive"))
      (node (ref "FPC1") (pin "23") (pinfunction "23_23") (pintype "passive"))
      (node (ref "V2") (pin "1") (pinfunction "GND_1") (pintype "passive"))
    )
    (net (code "85") (name "GND") (class "Default")
      (node (ref "C1") (pin "2") (pinfunction "2_2") (pintype "passive"))
      (node (ref "C10") (pin "1") (pinfunction "1_1") (pintype "passive"))
      (node (ref "C11") (pin "2") (pinfunction "2_2") (pintype "passive"))
      (node (ref "C12") (pin "2") (pinfunction "2_2") (pintype "passive"))
      (node (ref "C13") (pin "2") (pinfunction "2_2") (pintype "passive"))
      (node (ref "C14") (pin "2") (pinfunction "2_2") (pintype "passive"))
      (node (ref "C15") (pin "2") (pinfunction "2_2") (pintype "passive"))
      (node (ref "C17") (pin "2") (pinfunction "2_2") (pintype "passive"))
      (node (ref "C18") (pin "2") (pinfunction "2_2") (pintype "passive"))
      (node (ref "C19") (pin "2") (pinfunction "2_2") (pintype "passive"))
      (node (ref "C2") (pin "2") (pinfunction "2_2") (pintype "passive"))
      (node (ref "C20") (pin "2") (pinfunction "2_2") (pintype "passive"))
      (node (ref "C22") (pin "2") (pinfunction "2_2") (pintype "passive"))
      (node (ref "C23") (pin "1") (pinfunction "1_1") (pintype "passive"))
      (node (ref "C24") (pin "2") (pinfunction "2_2") (pintype "passive"))
      (node (ref "C26") (pin "2") (pinfunction "2_2") (pintype "passive"))
      (node (ref "C27") (pin "2") (pinfunction "2_2") (pintype "passive"))
      (node (ref "C28") (pin "2") (pinfunction "2_2") (pintype "passive"))
      (node (ref "C29") (pin "2") (pinfunction "2_2") (pintype "passive"))
      (node (ref "C3") (pin "1") (pinfunction "1_1") (pintype "passive"))
      (node (ref "C30") (pin "2") (pinfunction "2_2") (pintype "passive"))
      (node (ref "C31") (pin "2") (pinfunction "2_2") (pintype "passive"))
      (node (ref "C32") (pin "2") (pinfunction "2_2") (pintype "passive"))
      (node (ref "C33") (pin "2") (pinfunction "2_2") (pintype "passive"))
      (node (ref "C34") (pin "2") (pinfunction "2_2") (pintype "passive"))
      (node (ref "C35") (pin "2") (pinfunction "2_2") (pintype "passive"))
      (node (ref "C36") (pin "2") (pinfunction "2_2") (pintype "passive"))
      (node (ref "C37") (pin "2") (pinfunction "2_2") (pintype "passive"))
      (node (ref "C4") (pin "1") (pinfunction "1_1") (pintype "passive"))
      (node (ref "C42") (pin "1") (pinfunction "1_1") (pintype "passive"))
      (node (ref "C43") (pin "1") (pinfunction "1_1") (pintype "passive"))
      (node (ref "C44") (pin "1") (pinfunction "1_1") (pintype "passive"))
      (node (ref "C45") (pin "1") (pinfunction "1_1") (pintype "passive"))
      (node (ref "C46") (pin "1") (pinfunction "1_1") (pintype "passive"))
      (node (ref "C47") (pin "1") (pinfunction "1_1") (pintype "passive"))
      (node (ref "C48") (pin "1") (pinfunction "1_1") (pintype "passive"))
      (node (ref "C49") (pin "1") (pinfunction "1_1") (pintype "passive"))
      (node (ref "C5") (pin "1") (pinfunction "1_1") (pintype "passive"))
      (node (ref "C50") (pin "1") (pinfunction "1_1") (pintype "passive"))
      (node (ref "C51") (pin "1") (pinfunction "1_1") (pintype "passive"))
      (node (ref "C52") (pin "1") (pinfunction "1_1") (pintype "passive"))
      (node (ref "C53") (pin "1") (pinfunction "1_1") (pintype "passive"))
      (node (ref "C54") (pin "1") (pinfunction "1_1") (pintype "passive"))
      (node (ref "C55") (pin "1") (pinfunction "1_1") (pintype "passive"))
      (node (ref "C6") (pin "1") (pinfunction "1_1") (pintype "passive"))
      (node (ref "C7") (pin "2") (pinfunction "2_2") (pintype "passive"))
      (node (ref "C8") (pin "2") (pinfunction "2_2") (pintype "passive"))
      (node (ref "C9") (pin "1") (pinfunction "1_1") (pintype "passive"))
      (node (ref "D1") (pin "K") (pinfunction "K_K") (pintype "passive"))
      (node (ref "EA1") (pin "1") (pinfunction "GND3_1") (pintype "passive"))
      (node (ref "EA1") (pin "12") (pinfunction "GND1_12") (pintype "passive"))
      (node (ref "EA1") (pin "13") (pinfunction "AGND_13") (pintype "passive"))
      (node (ref "EA1") (pin "15") (pinfunction "AGND_15") (pintype "passive"))
      (node (ref "EA1") (pin "17") (pinfunction "AGND_17") (pintype "passive"))
      (node (ref "EA1") (pin "21") (pinfunction "PAD_21") (pintype "passive"))
      (node (ref "EA1") (pin "4") (pinfunction "AGND_4") (pintype "passive"))
      (node (ref "EA1") (pin "5") (pinfunction "GND2_5") (pintype "passive"))
      (node (ref "FB2") (pin "2") (pinfunction "2_2") (pintype "passive"))
      (node (ref "FPC1") (pin "10") (pinfunction "10_10") (pintype "passive"))
      (node (ref "J1") (pin "A1") (pinfunction "GND_A1") (pintype "passive"))
      (node (ref "J1") (pin "A12") (pinfunction "GND_A12") (pintype "passive"))
      (node (ref "J1") (pin "B1") (pinfunction "GND_B1") (pintype "passive"))
      (node (ref "J1") (pin "B12") (pinfunction "GND_B12") (pintype "passive"))
      (node (ref "J2") (pin "1") (pinfunction "LEDK_1") (pintype "passive"))
      (node (ref "J2") (pin "20") (pinfunction "GND_20") (pintype "passive"))
      (node (ref "J2") (pin "25") (pinfunction "pad_25") (pintype "passive"))
      (node (ref "J2") (pin "26") (pinfunction "pad_26") (pintype "passive"))
      (node (ref "J2") (pin "3") (pinfunction "GND_3") (pintype "passive"))
      (node (ref "JJ1") (pin "7") (pinfunction "7_7") (pintype "passive"))
      (node (ref "JJ3") (pin "1") (pinfunction "1_1") (pintype "passive"))
      (node (ref "MIC1") (pin "1") (pinfunction "GND_1") (pintype "passive"))
      (node (ref "P1") (pin "5") (pinfunction "5_5") (pintype "passive"))
      (node (ref "P2") (pin "1") (pinfunction "1_1") (pintype "passive"))
      (node (ref "R12") (pin "1") (pinfunction "1_1") (pintype "passive"))
      (node (ref "R15") (pin "1") (pinfunction "1_1") (pintype "passive"))
      (node (ref "R17") (pin "1") (pinfunction "1_1") (pintype "passive"))
      (node (ref "R20") (pin "1") (pinfunction "1_1") (pintype "passive"))
      (node (ref "S1") (pin "2") (pinfunction "2_2") (pintype "passive"))
      (node (ref "S2") (pin "2") (pinfunction "2_2") (pintype "passive"))
      (node (ref "TF1") (pin "10") (pinfunction "PAD1_10") (pintype "passive"))
      (node (ref "TF1") (pin "11") (pinfunction "PAD2_11") (pintype "passive"))
      (node (ref "TF1") (pin "12") (pinfunction "PAD3_12") (pintype "passive"))
      (node (ref "TF1") (pin "6") (pinfunction "GND_6") (pintype "passive"))
      (node (ref "TF1") (pin "9") (pinfunction "PAD4_9") (pintype "passive"))
      (node (ref "U1") (pin "1") (pinfunction "GND_1") (pintype "passive"))
      (node (ref "U1") (pin "7") (pinfunction "GND_7") (pintype "passive"))
      (node (ref "U2") (pin "C10") (pinfunction "VSS_C10") (pintype "power_in"))
      (node (ref "U2") (pin "C3") (pinfunction "VSS_C3") (pintype "power_in"))
      (node (ref "U2") (pin "C4") (pinfunction "VSS_C4") (pintype "power_in"))
      (node (ref "U2") (pin "C6") (pinfunction "VSS_C6") (pintype "power_in"))
      (node (ref "U2") (pin "C9") (pinfunction "VSS_C9") (pintype "power_in"))
      (node (ref "U2") (pin "D5") (pinfunction "VSS_D5") (pintype "power_in"))
      (node (ref "U2") (pin "D7") (pinfunction "VSS_D7") (pintype "power_in"))
      (node (ref "U2") (pin "D8") (pinfunction "VSS_D8") (pintype "power_in"))
      (node (ref "U2") (pin "E10") (pinfunction "VSS_E10") (pintype "power_in"))
      (node (ref "U2") (pin "E3") (pinfunction "VSS_E3") (pintype "power_in"))
      (node (ref "U2") (pin "E4") (pinfunction "VSS_E4") (pintype "power_in"))
      (node (ref "U2") (pin "E5") (pinfunction "VSS_E5") (pintype "power_in"))
      (node (ref "U2") (pin "E6") (pinfunction "VSS_E6") (pintype "power_in"))
      (node (ref "U2") (pin "E8") (pinfunction "VSS_E8") (pintype "power_in"))
      (node (ref "U2") (pin "F10") (pinfunction "VSS_F10") (pintype "power_in"))
      (node (ref "U2") (pin "F5") (pinfunction "VSS_F5") (pintype "power_in"))
      (node (ref "U2") (pin "F7") (pinfunction "VSS_F7") (pintype "power_in"))
      (node (ref "U2") (pin "F8") (pinfunction "VSS_F8") (pintype "power_in"))
      (node (ref "U2") (pin "F9") (pinfunction "VSS_F9") (pintype "power_in"))
      (node (ref "U2") (pin "G3") (pinfunction "VSS_G3") (pintype "power_in"))
      (node (ref "U2") (pin "G4") (pinfunction "VSS_G4") (pintype "power_in"))
      (node (ref "U2") (pin "G5") (pinfunction "VSS_G5") (pintype "power_in"))
      (node (ref "U2") (pin "G6") (pinfunction "VSS_G6") (pintype "power_in"))
      (node (ref "U2") (pin "G8") (pinfunction "VSS_G8") (pintype "power_in"))
      (node (ref "U2") (pin "H2") (pinfunction "VSS_H2") (pintype "power_in"))
      (node (ref "U2") (pin "H5") (pinfunction "VSS_H5") (pintype "power_in"))
      (node (ref "U2") (pin "H7") (pinfunction "VSS_H7") (pintype "power_in"))
      (node (ref "U2") (pin "H8") (pinfunction "VSS_H8") (pintype "power_in"))
      (node (ref "U2") (pin "H9") (pinfunction "VSS_H9") (pintype "power_in"))
      (node (ref "U2") (pin "J10") (pinfunction "VSS_J10") (pintype "power_in"))
      (node (ref "U2") (pin "J2") (pinfunction "VSS_J2") (pintype "power_in"))
      (node (ref "U2") (pin "J4") (pinfunction "VSS_J4") (pintype "power_in"))
      (node (ref "U2") (pin "J6") (pinfunction "VSS_J6") (pintype "power_in"))
      (node (ref "U2") (pin "J8") (pinfunction "VSS_J8") (pintype "power_in"))
      (node (ref "U2") (pin "K10") (pinfunction "VSS_K10") (pintype "power_in"))
      (node (ref "U2") (pin "K2") (pinfunction "VSS_K2") (pintype "power_in"))
      (node (ref "U2") (pin "K3") (pinfunction "VSS_K3") (pintype "power_in"))
      (node (ref "U2") (pin "K5") (pinfunction "VSS_K5") (pintype "power_in"))
      (node (ref "U2") (pin "K7") (pinfunction "VSS_K7") (pintype "power_in"))
      (node (ref "U2") (pin "K9") (pinfunction "VSS_K9") (pintype "power_in"))
      (node (ref "U2") (pin "L2") (pinfunction "VSS_L2") (pintype "power_in"))
      (node (ref "U3") (pin "1") (pinfunction "clkin_1") (pintype "passive"))
      (node (ref "U3") (pin "11") (pinfunction "psync_11") (pintype "passive"))
      (node (ref "U3") (pin "18") (pinfunction "gnd_18") (pintype "passive"))
      (node (ref "U3") (pin "9") (pinfunction "ado_9") (pintype "passive"))
      (node (ref "U4") (pin "2") (pinfunction "GND_2") (pintype "power_in"))
      (node (ref "U4") (pin "25") (pinfunction "GND_25") (pintype "power_in"))
      (node (ref "U5") (pin "1") (pinfunction "GND_1") (pintype "passive"))
      (node (ref "U6") (pin "4") (pinfunction "GND_4") (pintype "passive"))
      (node (ref "V1") (pin "1") (pinfunction "GND_1") (pintype "passive"))
      (node (ref "X1") (pin "2") (pinfunction "GND_2") (pintype "passive"))
      (node (ref "X1") (pin "4") (pinfunction "GND_4") (pintype "passive"))
    )
    (net (code "86") (name "Net-(D1-PadA)") (class "Default")
      (node (ref "D1") (pin "A") (pinfunction "A_A") (pintype "passive"))
      (node (ref "R10") (pin "2") (pinfunction "2_2") (pintype "passive"))
    )
    (net (code "87") (name "Net-(EA1-FB1)") (class "Default")
      (node (ref "C16") (pin "2") (pinfunction "2_2") (pintype "passive"))
      (node (ref "EA1") (pin "14") (pinfunction "FB1_14") (pintype "passive"))
      (node (ref "R11") (pin "1") (pinfunction "1_1") (pintype "passive"))
      (node (ref "R12") (pin "2") (pinfunction "2_2") (pintype "passive"))
    )
    (net (code "88") (name "Net-(EA1-FB2)") (class "Default")
      (node (ref "C21") (pin "2") (pinfunction "2_2") (pintype "passive"))
      (node (ref "EA1") (pin "3") (pinfunction "FB2_3") (pintype "passive"))
      (node (ref "R13") (pin "1") (pinfunction "1_1") (pintype "passive"))
      (node (ref "R15") (pin "2") (pinfunction "2_2") (pintype "passive"))
    )
    (net (code "89") (name "Net-(EA1-FB3)") (class "Default")
      (node (ref "C25") (pin "2") (pinfunction "2_2") (pintype "passive"))
      (node (ref "EA1") (pin "2") (pinfunction "FB3_2") (pintype "passive"))
      (node (ref "R16") (pin "1") (pinfunction "1_1") (pintype "passive"))
      (node (ref "R17") (pin "2") (pinfunction "2_2") (pintype "passive"))
    )
    (net (code "90") (name "Net-(EA1-SW1)") (class "Default")
      (node (ref "EA1") (pin "11") (pinfunction "SW1_11") (pintype "passive"))
      (node (ref "L1") (pin "1") (pinfunction "1_1") (pintype "passive"))
    )
    (net (code "91") (name "Net-(EA1-SW2)") (class "Default")
      (node (ref "EA1") (pin "6") (pinfunction "SW2_6") (pintype "passive"))
      (node (ref "L2") (pin "1") (pinfunction "1_1") (pintype "passive"))
    )
    (net (code "92") (name "Net-(EA1-SW3)") (class "Default")
      (node (ref "EA1") (pin "20") (pinfunction "SW3_20") (pintype "passive"))
      (node (ref "L3") (pin "1") (pinfunction "1_1") (pintype "passive"))
    )
    (net (code "93") (name "Net-(J2-LEDA)") (class "Default")
      (node (ref "J2") (pin "2") (pinfunction "LEDA_2") (pintype "passive"))
      (node (ref "R18") (pin "1") (pinfunction "1_1") (pintype "passive"))
    )
    (net (code "94") (name "Net-(P1-Pad7)") (class "Default")
      (node (ref "P1") (pin "7") (pinfunction "7_7") (pintype "passive"))
      (node (ref "P2") (pin "2") (pinfunction "2_2") (pintype "passive"))
    )
    (net (code "95") (name "Net-(RGB1-B)") (class "Default")
      (node (ref "R6") (pin "1") (pinfunction "1_1") (pintype "passive"))
      (node (ref "RGB1") (pin "3") (pinfunction "B_3") (pintype "passive"))
    )
    (net (code "96") (name "Net-(RGB1-G)") (class "Default")
      (node (ref "R5") (pin "2") (pinfunction "2_2") (pintype "passive"))
      (node (ref "RGB1") (pin "2") (pinfunction "G_2") (pintype "passive"))
    )
    (net (code "97") (name "Net-(RGB1-R)") (class "Default")
      (node (ref "R4") (pin "2") (pinfunction "2_2") (pintype "passive"))
      (node (ref "RGB1") (pin "1") (pinfunction "R_1") (pintype "passive"))
    )
    (net (code "98") (name "Net-(U2B-CLK)") (class "Default")
      (node (ref "U2") (pin "L3") (pinfunction "OSC_CLK_L3") (pintype "passive"))
      (node (ref "U2") (pin "M2") (pinfunction "CLK_M2") (pintype "passive"))
    )
    (net (code "99") (name "Net-(U2B-XTAL_IN)") (class "Default")
      (node (ref "C7") (pin "1") (pinfunction "1_1") (pintype "passive"))
      (node (ref "R9") (pin "2") (pinfunction "2_2") (pintype "passive"))
      (node (ref "U2") (pin "M4") (pinfunction "XTAL_IN_M4") (pintype "passive"))
      (node (ref "X1") (pin "1") (pinfunction "XI_1") (pintype "passive"))
    )
    (net (code "100") (name "Net-(U2B-XTAL_OUT)") (class "Default")
      (node (ref "C8") (pin "1") (pinfunction "1_1") (pintype "passive"))
      (node (ref "R9") (pin "1") (pinfunction "1_1") (pintype "passive"))
      (node (ref "U2") (pin "M3") (pinfunction "XTAL_OUT_M3") (pintype "passive"))
      (node (ref "X1") (pin "3") (pinfunction "XO_3") (pintype "passive"))
    )
    (net (code "101") (name "Net-(U2C-VDDOTP)") (class "Default")
      (node (ref "C23") (pin "2") (pinfunction "2_2") (pintype "passive"))
      (node (ref "R14") (pin "2") (pinfunction "2_2") (pintype "passive"))
      (node (ref "U2") (pin "J3") (pinfunction "VDDOTP_J3") (pintype "power_in"))
    )
    (net (code "102") (name "Net-(U2C-VDDPLL)") (class "Default")
      (node (ref "C38") (pin "2") (pinfunction "2_2") (pintype "passive"))
      (node (ref "C56") (pin "2") (pinfunction "2_2") (pintype "passive"))
      (node (ref "R19") (pin "1") (pinfunction "1_1") (pintype "passive"))
      (node (ref "U2") (pin "L4") (pinfunction "VDDPLL_L4") (pintype "power_in"))
    )
    (net (code "103") (name "Net-(U2C-VSSPLL)") (class "Default")
      (node (ref "C38") (pin "1") (pinfunction "1_1") (pintype "passive"))
      (node (ref "C56") (pin "1") (pinfunction "1_1") (pintype "passive"))
      (node (ref "R20") (pin "2") (pinfunction "2_2") (pintype "passive"))
      (node (ref "U2") (pin "K4") (pinfunction "VSSPLL_K4") (pintype "power_in"))
    )
    (net (code "104") (name "Net-(U3-cpout)") (class "Default")
      (node (ref "C1") (pin "1") (pinfunction "1_1") (pintype "passive"))
      (node (ref "U3") (pin "20") (pinfunction "cpout_20") (pintype "passive"))
    )
    (net (code "105") (name "Net-(U3-regout)") (class "Default")
      (node (ref "C5") (pin "2") (pinfunction "2_2") (pintype "passive"))
      (node (ref "U3") (pin "10") (pinfunction "regout_10") (pintype "passive"))
    )
    (net (code "106") (name "Net-(U4-VDD)") (class "Default")
      (node (ref "C2") (pin "1") (pinfunction "1_1") (pintype "passive"))
      (node (ref "R1") (pin "2") (pinfunction "2_2") (pintype "passive"))
      (node (ref "U4") (pin "5") (pinfunction "VIO_5") (pintype "passive"))
      (node (ref "U4") (pin "6") (pinfunction "VDD_6") (pintype "passive"))
    )
    (net (code "107") (name "Net-(U4-~{RS}T)") (class "Default")
      (node (ref "R1") (pin "1") (pinfunction "1_1") (pintype "passive"))
      (node (ref "U4") (pin "9") (pinfunction "~{RS}T_9") (pintype "passive"))
    )
    (net (code "108") (name "Net-(V2-Vin)") (class "Default")
      (node (ref "C39") (pin "1") (pinfunction "1_1") (pintype "passive"))
      (node (ref "FB1") (pin "1") (pinfunction "1_1") (pintype "passive"))
      (node (ref "V2") (pin "3") (pinfunction "Vin_3") (pintype "passive"))
    )
    (net (code "109") (name "VCC3V3") (class "Default")
      (node (ref "R3") (pin "1") (pinfunction "1_1") (pintype "passive"))
      (node (ref "U5") (pin "3") (pinfunction "VCC_3") (pintype "passive"))
    )
    (net (code "110") (name "unconnected-(FPC1-Pad1)") (class "Default")
      (node (ref "FPC1") (pin "1") (pinfunction "1_1") (pintype "passive+no_connect"))
    )
    (net (code "111") (name "unconnected-(FPC1-Pad2)") (class "Default")
      (node (ref "FPC1") (pin "2") (pinfunction "2_2") (pintype "passive+no_connect"))
    )
    (net (code "112") (name "unconnected-(FPC1-Pad24)") (class "Default")
      (node (ref "FPC1") (pin "24") (pinfunction "24_24") (pintype "passive+no_connect"))
    )
    (net (code "113") (name "unconnected-(J1-CC1-PadA5)") (class "Default")
      (node (ref "J1") (pin "A5") (pinfunction "CC1_A5") (pintype "passive"))
    )
    (net (code "114") (name "unconnected-(J1-CC2-PadB5)") (class "Default")
      (node (ref "J1") (pin "B5") (pinfunction "CC2_B5") (pintype "passive"))
    )
    (net (code "115") (name "unconnected-(J1-SBU1-PadA8)") (class "Default")
      (node (ref "J1") (pin "A8") (pinfunction "SBU1_A8") (pintype "passive"))
    )
    (net (code "116") (name "unconnected-(J1-SBU2-PadB8)") (class "Default")
      (node (ref "J1") (pin "B8") (pinfunction "SBU2_B8") (pintype "passive"))
    )
    (net (code "117") (name "unconnected-(J1-pad-Pad0)") (class "Default")
      (node (ref "J1") (pin "0") (pinfunction "pad_0") (pintype "passive+no_connect"))
    )
    (net (code "118") (name "unconnected-(J1-pad-Pad0)_1") (class "Default")
      (node (ref "J1") (pin "0") (pinfunction "pad_0") (pintype "passive+no_connect"))
    )
    (net (code "119") (name "unconnected-(J1-pad-Pad0)_2") (class "Default")
      (node (ref "J1") (pin "0") (pinfunction "pad_0") (pintype "passive+no_connect"))
    )
    (net (code "120") (name "unconnected-(J1-pad-Pad0)_3") (class "Default")
      (node (ref "J1") (pin "0") (pinfunction "pad_0") (pintype "passive+no_connect"))
    )
    (net (code "121") (name "unconnected-(J2-NC-Pad6)") (class "Default")
      (node (ref "J2") (pin "6") (pinfunction "NC_6") (pintype "passive+no_connect"))
    )
    (net (code "122") (name "unconnected-(J2-NC-Pad21)") (class "Default")
      (node (ref "J2") (pin "21") (pinfunction "NC_21") (pintype "passive+no_connect"))
    )
    (net (code "123") (name "unconnected-(J2-NC-Pad22)") (class "Default")
      (node (ref "J2") (pin "22") (pinfunction "NC_22") (pintype "passive+no_connect"))
    )
    (net (code "124") (name "unconnected-(J2-NC-Pad23)") (class "Default")
      (node (ref "J2") (pin "23") (pinfunction "NC_23") (pintype "passive+no_connect"))
    )
    (net (code "125") (name "unconnected-(J2-NC-Pad24)") (class "Default")
      (node (ref "J2") (pin "24") (pinfunction "NC_24") (pintype "passive+no_connect"))
    )
    (net (code "126") (name "unconnected-(MIC1-NC-Pad2)") (class "Default")
      (node (ref "MIC1") (pin "2") (pinfunction "NC_2") (pintype "passive+no_connect"))
    )
    (net (code "127") (name "unconnected-(P1-Pad3)") (class "Default")
      (node (ref "P1") (pin "3") (pinfunction "3_3") (pintype "passive"))
    )
    (net (code "128") (name "unconnected-(P1-Pad6)") (class "Default")
      (node (ref "P1") (pin "6") (pinfunction "6_6") (pintype "passive"))
    )
    (net (code "129") (name "unconnected-(TF1-DAT1-Pad8)") (class "Default")
      (node (ref "TF1") (pin "8") (pinfunction "DAT1_8") (pintype "passive+no_connect"))
    )
    (net (code "130") (name "unconnected-(TF1-DAT2-Pad1)") (class "Default")
      (node (ref "TF1") (pin "1") (pinfunction "DAT2_1") (pintype "passive+no_connect"))
    )
    (net (code "131") (name "unconnected-(U2A-IO_11-PadE12)") (class "Default")
      (node (ref "U2") (pin "E12") (pinfunction "IO_11_E12") (pintype "passive"))
    )
    (net (code "132") (name "unconnected-(U2A-IO_15-PadC12)") (class "Default")
      (node (ref "U2") (pin "C12") (pinfunction "IO_15_C12") (pintype "passive"))
    )
    (net (code "133") (name "unconnected-(U2A-IO_17-PadA12)") (class "Default")
      (node (ref "U2") (pin "A12") (pinfunction "IO_17_A12") (pintype "passive"))
    )
    (net (code "134") (name "unconnected-(U3-Pad2)") (class "Default")
      (node (ref "U3") (pin "2") (pinfunction "2_2") (pintype "passive"))
    )
    (net (code "135") (name "unconnected-(U3-Pad3)") (class "Default")
      (node (ref "U3") (pin "3") (pinfunction "3_3") (pintype "passive"))
    )
    (net (code "136") (name "unconnected-(U3-Pad4)") (class "Default")
      (node (ref "U3") (pin "4") (pinfunction "4_4") (pintype "passive"))
    )
    (net (code "137") (name "unconnected-(U3-Pad5)") (class "Default")
      (node (ref "U3") (pin "5") (pinfunction "5_5") (pintype "passive"))
    )
    (net (code "138") (name "unconnected-(U3-Pad14)") (class "Default")
      (node (ref "U3") (pin "14") (pinfunction "14_14") (pintype "passive"))
    )
    (net (code "139") (name "unconnected-(U3-Pad15)") (class "Default")
      (node (ref "U3") (pin "15") (pinfunction "15_15") (pintype "passive"))
    )
    (net (code "140") (name "unconnected-(U3-Pad16)") (class "Default")
      (node (ref "U3") (pin "16") (pinfunction "16_16") (pintype "passive"))
    )
    (net (code "141") (name "unconnected-(U3-Pad17)") (class "Default")
      (node (ref "U3") (pin "17") (pinfunction "17_17") (pintype "passive"))
    )
    (net (code "142") (name "unconnected-(U3-aux_cl-Pad7)") (class "Default")
      (node (ref "U3") (pin "7") (pinfunction "aux_cl_7") (pintype "passive"))
    )
    (net (code "143") (name "unconnected-(U3-aux_da-Pad6)") (class "Default")
      (node (ref "U3") (pin "6") (pinfunction "aux_da_6") (pintype "passive"))
    )
    (net (code "144") (name "unconnected-(U3-clkout-Pad22)") (class "Default")
      (node (ref "U3") (pin "22") (pinfunction "clkout_22") (pintype "passive"))
    )
    (net (code "145") (name "unconnected-(U3-int-Pad12)") (class "Default")
      (node (ref "U3") (pin "12") (pinfunction "int_12") (pintype "passive"))
    )
    (net (code "146") (name "unconnected-(U3-resv-Pad19)") (class "Default")
      (node (ref "U3") (pin "19") (pinfunction "resv_19") (pintype "passive"))
    )
    (net (code "147") (name "unconnected-(U3-resv-Pad21)") (class "Default")
      (node (ref "U3") (pin "21") (pinfunction "resv_21") (pintype "passive"))
    )
    (net (code "148") (name "unconnected-(U4-CTS-Pad18)") (class "Default")
      (node (ref "U4") (pin "18") (pinfunction "CTS_18") (pintype "passive+no_connect"))
    )
    (net (code "149") (name "unconnected-(U4-DCD-Pad24)") (class "Default")
      (node (ref "U4") (pin "24") (pinfunction "DCD_24") (pintype "passive+no_connect"))
    )
    (net (code "150") (name "unconnected-(U4-DSR-Pad22)") (class "Default")
      (node (ref "U4") (pin "22") (pinfunction "DSR_22") (pintype "passive+no_connect"))
    )
    (net (code "151") (name "unconnected-(U4-GPIO.2-Pad12)") (class "Default")
      (node (ref "U4") (pin "12") (pinfunction "GPIO.2_12") (pintype "passive"))
    )
    (net (code "152") (name "unconnected-(U4-GPIO.3-Pad11)") (class "Default")
      (node (ref "U4") (pin "11") (pinfunction "GPIO.3_11") (pintype "passive"))
    )
    (net (code "153") (name "unconnected-(U4-NC-Pad10)") (class "Default")
      (node (ref "U4") (pin "10") (pinfunction "NC_10") (pintype "passive"))
    )
    (net (code "154") (name "unconnected-(U4-RI-Pad1)") (class "Default")
      (node (ref "U4") (pin "1") (pinfunction "RI_1") (pintype "passive+no_connect"))
    )
    (net (code "155") (name "unconnected-(U4-SUSPEND-Pad17)") (class "Default")
      (node (ref "U4") (pin "17") (pinfunction "SUSPEND_17") (pintype "passive+no_connect"))
    )
    (net (code "156") (name "unconnected-(U4-VPP-Pad16)") (class "Default")
      (node (ref "U4") (pin "16") (pinfunction "VPP_16") (pintype "passive"))
    )
    (net (code "157") (name "unconnected-(U4-~{SUSPEND}-Pad15)") (class "Default")
      (node (ref "U4") (pin "15") (pinfunction "~{SUSPEND}_15") (pintype "passive+no_connect"))
    )
  )
)
